# Transformer_Powder.net
KiCad netlist of a schematic drawn in Altium Designer
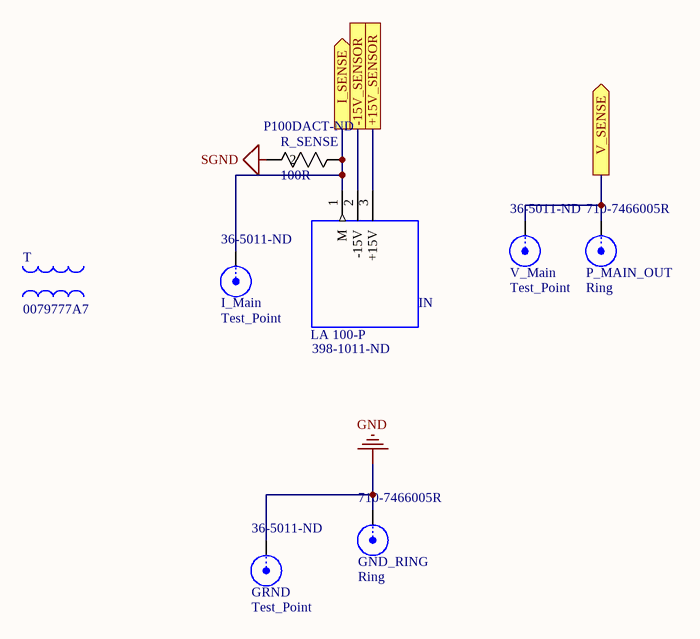
[diagram p0: Transformer_Powder.SchDoc]

(export (version "E")
  (design (tool "Eeschema 10.0.6"))
  (components
    (comp (ref "GND_RING")
      (value "Ring")
      (footprint "7466005R")
      (description "Ring Connector")
      (fields
        (field (name "SUPPLIER PART NUMBER 1") "710-7466005R")
        (field (name "MANUFACTURER") "Wurth Electronics")
        (field (name "MANUFACTURER PART NUMBER") "7466005R")
      )
      (libsource (lib "Miscellaneous Connectors") (part "BNC"))
    )
    (comp (ref "GRND")
      (value "Test_Point")
      (footprint "5011")
      (fields
        (field (name "SUPPLIER PART NUMBER 1") "36-5011-ND")
        (field (name "MANUFACTURER") "Keystone Electronics")
        (field (name "MANUFACTURER PART NUMBER") "5011")
      )
      (libsource (lib "Miscellaneous Connectors") (part "BNC"))
    )
    (comp (ref "I_Main")
      (value "Test_Point")
      (footprint "5011")
      (fields
        (field (name "SUPPLIER PART NUMBER 1") "36-5011-ND")
        (field (name "MANUFACTURER") "Keystone Electronics")
        (field (name "MANUFACTURER PART NUMBER") "5011")
      )
      (libsource (lib "Miscellaneous Connectors") (part "BNC"))
    )
    (comp (ref "LA 100-P")
      (value "IN")
      (footprint "LA 100-P")
      (description "Current Transducer LA series")
      (fields
        (field (name "SUPPLIER PART NUMBER 1") "398-1011-ND")
        (field (name "MANUFACTURER") "LEM")
        (field (name "MANUFACTURER PART NUMBER") "LA100-P")
      )
      (libsource (lib "LKSR_6-NP") (part "LKSR_6-NP"))
    )
    (comp (ref "P_MAIN_OUT")
      (value "Ring")
      (footprint "7466005R")
      (description "Ring Connector")
      (fields
        (field (name "SUPPLIER PART NUMBER 1") "710-7466005R")
        (field (name "MANUFACTURER") "Wurth Electronics")
        (field (name "MANUFACTURER PART NUMBER") "7466005R")
      )
      (libsource (lib "Miscellaneous Connectors") (part "BNC"))
    )
    (comp (ref "R_SENSE")
      (value "100R")
      (footprint "RES_ERA6A_0805")
      (description "No Description Available")
      (fields
        (field (name "MANUFACTURER_PART_NUMBER") "ERA6AEB101V")
        (field (name "SUPPLIER PART NUMBER 1") "P100DACT-ND")
        (field (name "MANUFACTURER") "Panasonic")
        (field (name "COPYRIGHT") "Copyright (C) 2018 Accelerated Designs. All rights reserved")
      )
      (libsource (lib "ERA-6AEB101V") (part "ERA6AEB101V"))
    )
    (comp (ref "T")
      (value "0079777A7")
      (footprint "Fat_Man")
      (description "Transformer")
      (libsource (lib "Miscellaneous Devices") (part "Trans"))
    )
    (comp (ref "V_Main")
      (value "Test_Point")
      (footprint "5011")
      (fields
        (field (name "SUPPLIER PART NUMBER 1") "36-5011-ND")
        (field (name "MANUFACTURER") "Keystone Electronics")
        (field (name "MANUFACTURER PART NUMBER") "5011")
      )
      (libsource (lib "Miscellaneous Connectors") (part "BNC"))
    )
  )
  (nets
    (net (code "1") (name "/+15V_SENSOR") (class "Default")
      (node (ref "LA 100-P") (pin "3") (pinfunction "+15V_3") (pintype "power_in"))
    )
    (net (code "2") (name "/-15V_SENSOR") (class "Default")
      (node (ref "LA 100-P") (pin "2") (pinfunction "-15V_2") (pintype "power_in"))
    )
    (net (code "3") (name "/I_SENSE") (class "Default")
      (node (ref "I_Main") (pin "1") (pinfunction "X_1") (pintype "passive"))
      (node (ref "LA 100-P") (pin "1") (pinfunction "M_1") (pintype "output"))
      (node (ref "R_SENSE") (pin "1") (pinfunction "1_1") (pintype "passive"))
    )
    (net (code "4") (name "/V_SENSE") (class "Default")
      (node (ref "P_MAIN_OUT") (pin "1") (pinfunction "X_1") (pintype "passive"))
      (node (ref "V_Main") (pin "1") (pinfunction "X_1") (pintype "passive"))
    )
    (net (code "5") (name "GND") (class "Default")
      (node (ref "GND_RING") (pin "1") (pinfunction "X_1") (pintype "passive"))
      (node (ref "GRND") (pin "1") (pinfunction "X_1") (pintype "passive"))
    )
    (net (code "6") (name "SGND") (class "Default")
      (node (ref "R_SENSE") (pin "2") (pinfunction "2_2") (pintype "passive"))
    )
  )
)
